# USB-to-ESP-UART_v3_1.net
KiCad netlist of a schematic drawn in EAGLE
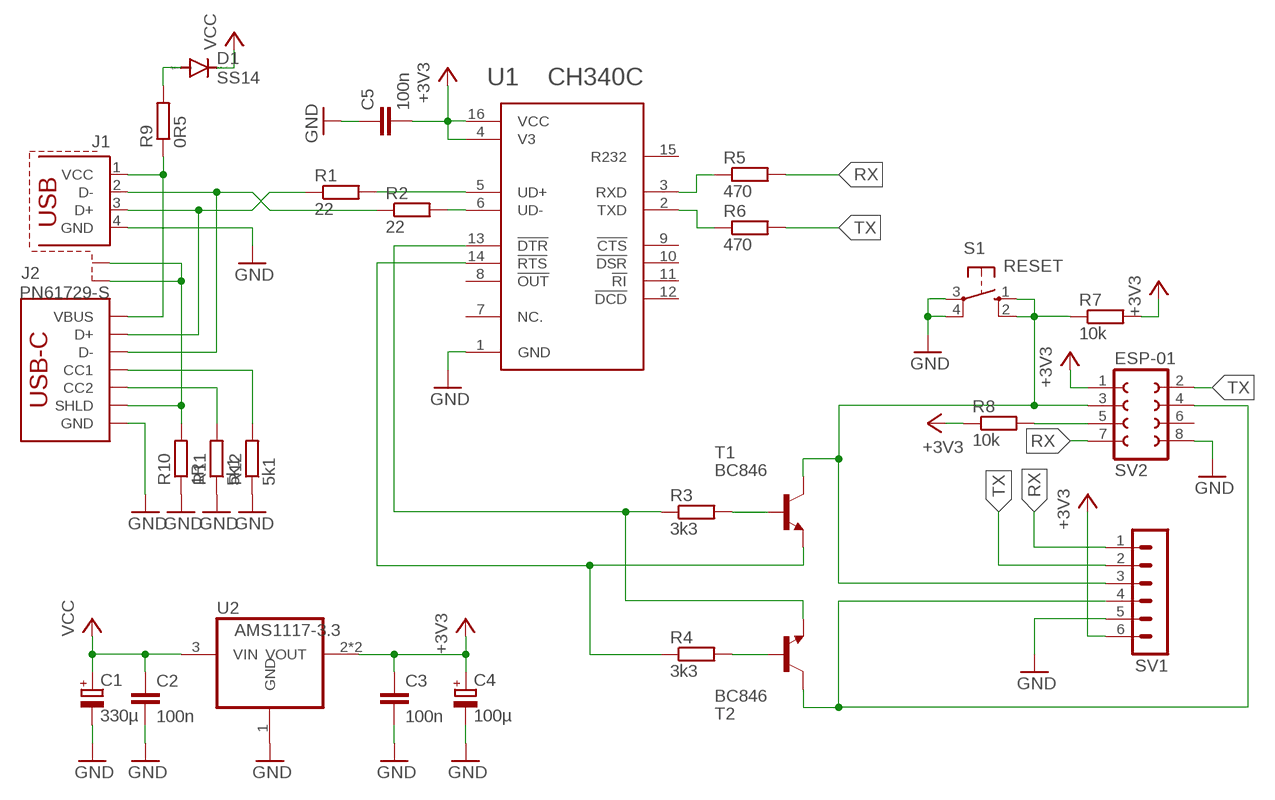
[diagram p0: schematic, sheet 1]

(export (version "E")
  (design (tool "Eeschema 10.0.6"))
  (components
    (comp (ref "C1")
      (value "330µ")
      (footprint "eagle-import:E2,5-7")
      (libsource (lib "eagle-import") (part "CPOL-EUE2.5-7"))
    )
    (comp (ref "C2")
      (value "100n")
      (footprint "eagle-import:C1206")
      (libsource (lib "eagle-import") (part "C-EUC1206"))
    )
    (comp (ref "C3")
      (value "100n")
      (footprint "eagle-import:C1206")
      (libsource (lib "eagle-import") (part "C-EUC1206"))
    )
    (comp (ref "C4")
      (value "100µ")
      (footprint "eagle-import:E2,5-5")
      (libsource (lib "eagle-import") (part "CPOL-EUE2.5-5"))
    )
    (comp (ref "C5")
      (value "100n")
      (footprint "eagle-import:C1206")
      (libsource (lib "eagle-import") (part "C-EUC1206"))
    )
    (comp (ref "D1")
      (value "SS14")
      (footprint "eagle-import:DO214AC")
      (libsource (lib "eagle-import") (part "DIODE-DO214AC"))
    )
    (comp (ref "J1")
      (value "PN61729-S")
      (footprint "eagle-import:PN61729-S")
      (libsource (lib "eagle-import") (part "PN61729-S"))
    )
    (comp (ref "J2")
      (value "USB_C_2-LAYER_PADS")
      (footprint "eagle-import:USB-C-16P-2LAYER-PADS")
      (libsource (lib "eagle-import") (part "USB_C_2-LAYER_PADS"))
    )
    (comp (ref "R1")
      (value "22")
      (footprint "eagle-import:R1206")
      (libsource (lib "eagle-import") (part "R-EU_R1206"))
    )
    (comp (ref "R2")
      (value "22")
      (footprint "eagle-import:R1206")
      (libsource (lib "eagle-import") (part "R-EU_R1206"))
    )
    (comp (ref "R3")
      (value "3k3")
      (footprint "eagle-import:R1206")
      (libsource (lib "eagle-import") (part "R-EU_R1206"))
    )
    (comp (ref "R4")
      (value "3k3")
      (footprint "eagle-import:R1206")
      (libsource (lib "eagle-import") (part "R-EU_R1206"))
    )
    (comp (ref "R5")
      (value "470")
      (footprint "eagle-import:R1206")
      (libsource (lib "eagle-import") (part "R-EU_R1206"))
    )
    (comp (ref "R6")
      (value "470")
      (footprint "eagle-import:R1206")
      (libsource (lib "eagle-import") (part "R-EU_R1206"))
    )
    (comp (ref "R7")
      (value "10k")
      (footprint "eagle-import:R1206")
      (libsource (lib "eagle-import") (part "R-EU_R1206"))
    )
    (comp (ref "R8")
      (value "10k")
      (footprint "eagle-import:R1206")
      (libsource (lib "eagle-import") (part "R-EU_R1206"))
    )
    (comp (ref "R9")
      (value "0R5")
      (footprint "eagle-import:R1206")
      (libsource (lib "eagle-import") (part "R-EU_R1206"))
    )
    (comp (ref "R10")
      (value "1R")
      (footprint "eagle-import:R1206")
      (libsource (lib "eagle-import") (part "R-EU_R1206"))
    )
    (comp (ref "R11")
      (value "5k1")
      (footprint "eagle-import:R1206")
      (libsource (lib "eagle-import") (part "R-EU_R1206"))
    )
    (comp (ref "R12")
      (value "5k1")
      (footprint "eagle-import:R1206")
      (libsource (lib "eagle-import") (part "R-EU_R1206"))
    )
    (comp (ref "S1")
      (value "RESET")
      (footprint "eagle-import:B3F-10XX")
      (fields (field (name "MPN") "B3F-1000"))
      (libsource (lib "eagle-import") (part "10-XX"))
    )
    (comp (ref "SV1")
      (value "MA06-1")
      (footprint "eagle-import:MA06-1")
      (libsource (lib "eagle-import") (part "MA06-1"))
    )
    (comp (ref "SV2")
      (value "ESP-01")
      (footprint "eagle-import:FE04-2-CL")
      (libsource (lib "eagle-import") (part "FE04-2CLEAN"))
    )
    (comp (ref "T1")
      (value "BC846")
      (footprint "eagle-import:SOT23-BEC")
      (libsource (lib "eagle-import") (part "-NPN-SOT23-BECBC846A"))
    )
    (comp (ref "T2")
      (value "BC846")
      (footprint "eagle-import:SOT23-BEC")
      (libsource (lib "eagle-import") (part "-NPN-SOT23-BECBC846A"))
    )
    (comp (ref "U1")
      (value "CH340C")
      (footprint "eagle-import:SOIC127P600X180-16N")
      (fields (field (name "MF") "WCH"))
      (libsource (lib "eagle-import") (part "CH340C"))
    )
    (comp (ref "U2")
      (value "AMS1117-3.3")
      (footprint "eagle-import:SOT223")
      (fields (field (name "MPN") "REG1117"))
      (libsource (lib "eagle-import") (part "REG1117"))
    )
  )
  (nets
    (net (code "1") (name "+3V3") (class "Default")
      (node (ref "C3") (pin "1") (pinfunction "1_1") (pintype "passive"))
      (node (ref "C4") (pin "+") (pinfunction "+_+") (pintype "passive"))
      (node (ref "C5") (pin "2") (pinfunction "2_2") (pintype "passive"))
      (node (ref "R7") (pin "2") (pinfunction "2_2") (pintype "passive"))
      (node (ref "R8") (pin "1") (pinfunction "1_1") (pintype "passive"))
      (node (ref "SV1") (pin "6") (pinfunction "6_6") (pintype "passive"))
      (node (ref "SV2") (pin "1") (pinfunction "1_1") (pintype "passive"))
      (node (ref "U1") (pin "16") (pinfunction "VCC_16") (pintype "power_in"))
      (node (ref "U1") (pin "4") (pinfunction "V3_4") (pintype "power_in"))
      (node (ref "U2") (pin "2") (pinfunction "VOUT_2") (pintype "output"))
      (node (ref "U2") (pin "4") (pinfunction "VOUT_4") (pintype "output"))
    )
    (net (code "2") (name "GND") (class "Default")
      (node (ref "C1") (pin "-") (pinfunction "-_-") (pintype "passive"))
      (node (ref "C2") (pin "2") (pinfunction "2_2") (pintype "passive"))
      (node (ref "C3") (pin "2") (pinfunction "2_2") (pintype "passive"))
      (node (ref "C4") (pin "-") (pinfunction "-_-") (pintype "passive"))
      (node (ref "C5") (pin "1") (pinfunction "1_1") (pintype "passive"))
      (node (ref "J1") (pin "4") (pinfunction "GND_4") (pintype "passive"))
      (node (ref "J2") (pin "GND") (pinfunction "GND_GND") (pintype "bidirectional"))
      (node (ref "J2") (pin "GND2") (pinfunction "GND_GND2") (pintype "bidirectional"))
      (node (ref "R10") (pin "1") (pinfunction "1_1") (pintype "passive"))
      (node (ref "R11") (pin "1") (pinfunction "1_1") (pintype "passive"))
      (node (ref "R12") (pin "1") (pinfunction "1_1") (pintype "passive"))
      (node (ref "S1") (pin "3") (pinfunction "P_3") (pintype "passive"))
      (node (ref "S1") (pin "4") (pinfunction "P1_4") (pintype "passive"))
      (node (ref "SV1") (pin "5") (pinfunction "5_5") (pintype "passive"))
      (node (ref "SV2") (pin "8") (pinfunction "8_8") (pintype "passive"))
      (node (ref "U1") (pin "1") (pinfunction "GND_1") (pintype "power_in"))
      (node (ref "U2") (pin "1") (pinfunction "GND_1") (pintype "power_in"))
    )
    (net (code "3") (name "Net-(D1-PadA)") (class "Default")
      (node (ref "D1") (pin "A") (pinfunction "A_A") (pintype "passive"))
      (node (ref "R9") (pin "2") (pinfunction "2_2") (pintype "passive"))
    )
    (net (code "4") (name "Net-(J1-D+)") (class "Default")
      (node (ref "J1") (pin "3") (pinfunction "D+_3") (pintype "passive"))
      (node (ref "J2") (pin "A6") (pinfunction "D+_A6") (pintype "bidirectional"))
      (node (ref "J2") (pin "B6") (pinfunction "D+_B6") (pintype "bidirectional"))
      (node (ref "R1") (pin "1") (pinfunction "1_1") (pintype "passive"))
    )
    (net (code "5") (name "Net-(J1-D-)") (class "Default")
      (node (ref "J1") (pin "2") (pinfunction "D-_2") (pintype "passive"))
      (node (ref "J2") (pin "A7") (pinfunction "D-_A7") (pintype "bidirectional"))
      (node (ref "J2") (pin "B7") (pinfunction "D-_B7") (pintype "bidirectional"))
      (node (ref "R2") (pin "1") (pinfunction "1_1") (pintype "passive"))
    )
    (net (code "6") (name "Net-(J1-PadS1)") (class "Default")
      (node (ref "J1") (pin "S1") (pinfunction "S1_S1") (pintype "passive"))
      (node (ref "J1") (pin "S2") (pinfunction "S2_S2") (pintype "passive"))
      (node (ref "J2") (pin "SHLD1") (pinfunction "SHLD_SHLD1") (pintype "bidirectional"))
      (node (ref "J2") (pin "SHLD2") (pinfunction "SHLD_SHLD2") (pintype "bidirectional"))
      (node (ref "J2") (pin "SHLD3") (pinfunction "SHLD_SHLD3") (pintype "bidirectional"))
      (node (ref "J2") (pin "SHLD4") (pinfunction "SHLD_SHLD4") (pintype "bidirectional"))
      (node (ref "R10") (pin "2") (pinfunction "2_2") (pintype "passive"))
    )
    (net (code "7") (name "Net-(J1-VCC)") (class "Default")
      (node (ref "J1") (pin "1") (pinfunction "VCC_1") (pintype "passive"))
      (node (ref "J2") (pin "VBUS1") (pinfunction "VBUS_VBUS1") (pintype "bidirectional"))
      (node (ref "J2") (pin "VBUS2") (pinfunction "VBUS_VBUS2") (pintype "bidirectional"))
      (node (ref "R9") (pin "1") (pinfunction "1_1") (pintype "passive"))
    )
    (net (code "8") (name "Net-(J2-CC1)") (class "Default")
      (node (ref "J2") (pin "A5") (pinfunction "CC1_A5") (pintype "bidirectional"))
      (node (ref "R12") (pin "2") (pinfunction "2_2") (pintype "passive"))
    )
    (net (code "9") (name "Net-(J2-CC2)") (class "Default")
      (node (ref "J2") (pin "B5") (pinfunction "CC2_B5") (pintype "bidirectional"))
      (node (ref "R11") (pin "2") (pinfunction "2_2") (pintype "passive"))
    )
    (net (code "10") (name "Net-(R3-Pad2)") (class "Default")
      (node (ref "R3") (pin "2") (pinfunction "2_2") (pintype "passive"))
      (node (ref "T1") (pin "B") (pinfunction "B_B") (pintype "passive"))
    )
    (net (code "11") (name "Net-(R4-Pad2)") (class "Default")
      (node (ref "R4") (pin "2") (pinfunction "2_2") (pintype "passive"))
      (node (ref "T2") (pin "B") (pinfunction "B_B") (pintype "passive"))
    )
    (net (code "12") (name "Net-(R8-Pad2)") (class "Default")
      (node (ref "R8") (pin "2") (pinfunction "2_2") (pintype "passive"))
      (node (ref "SV2") (pin "5") (pinfunction "5_5") (pintype "passive"))
    )
    (net (code "13") (name "Net-(S1-S)") (class "Default")
      (node (ref "R7") (pin "1") (pinfunction "1_1") (pintype "passive"))
      (node (ref "S1") (pin "1") (pinfunction "S_1") (pintype "passive"))
      (node (ref "S1") (pin "2") (pinfunction "S1_2") (pintype "passive"))
      (node (ref "SV1") (pin "3") (pinfunction "3_3") (pintype "passive"))
      (node (ref "SV2") (pin "3") (pinfunction "3_3") (pintype "passive"))
      (node (ref "T1") (pin "C") (pinfunction "C_C") (pintype "passive"))
    )
    (net (code "14") (name "Net-(SV1-Pad4)") (class "Default")
      (node (ref "SV1") (pin "4") (pinfunction "4_4") (pintype "passive"))
      (node (ref "SV2") (pin "4") (pinfunction "4_4") (pintype "passive"))
      (node (ref "T2") (pin "C") (pinfunction "C_C") (pintype "passive"))
    )
    (net (code "15") (name "Net-(U1-RXD)") (class "Default")
      (node (ref "R5") (pin "1") (pinfunction "1_1") (pintype "passive"))
      (node (ref "U1") (pin "3") (pinfunction "RXD_3") (pintype "input"))
    )
    (net (code "16") (name "Net-(U1-TXD)") (class "Default")
      (node (ref "R6") (pin "1") (pinfunction "1_1") (pintype "passive"))
      (node (ref "U1") (pin "2") (pinfunction "TXD_2") (pintype "output"))
    )
    (net (code "17") (name "Net-(U1-UD+)") (class "Default")
      (node (ref "R1") (pin "2") (pinfunction "2_2") (pintype "passive"))
      (node (ref "U1") (pin "5") (pinfunction "UD+_5") (pintype "bidirectional"))
    )
    (net (code "18") (name "Net-(U1-UD-)") (class "Default")
      (node (ref "R2") (pin "2") (pinfunction "2_2") (pintype "passive"))
      (node (ref "U1") (pin "6") (pinfunction "UD-_6") (pintype "bidirectional"))
    )
    (net (code "19") (name "Net-(U1-~{DTR})") (class "Default")
      (node (ref "R3") (pin "1") (pinfunction "1_1") (pintype "passive"))
      (node (ref "T2") (pin "E") (pinfunction "E_E") (pintype "passive"))
      (node (ref "U1") (pin "13") (pinfunction "~{DTR}_13") (pintype "output"))
    )
    (net (code "20") (name "Net-(U1-~{RTS})") (class "Default")
      (node (ref "R4") (pin "1") (pinfunction "1_1") (pintype "passive"))
      (node (ref "T1") (pin "E") (pinfunction "E_E") (pintype "passive"))
      (node (ref "U1") (pin "14") (pinfunction "~{RTS}_14") (pintype "output"))
    )
    (net (code "21") (name "RX") (class "Default")
      (node (ref "R5") (pin "2") (pinfunction "2_2") (pintype "passive"))
      (node (ref "SV1") (pin "1") (pinfunction "1_1") (pintype "passive"))
      (node (ref "SV2") (pin "7") (pinfunction "7_7") (pintype "passive"))
    )
    (net (code "22") (name "TX") (class "Default")
      (node (ref "R6") (pin "2") (pinfunction "2_2") (pintype "passive"))
      (node (ref "SV1") (pin "2") (pinfunction "2_2") (pintype "passive"))
      (node (ref "SV2") (pin "2") (pinfunction "2_2") (pintype "passive"))
    )
    (net (code "23") (name "VCC") (class "Default")
      (node (ref "C1") (pin "+") (pinfunction "+_+") (pintype "passive"))
      (node (ref "C2") (pin "1") (pinfunction "1_1") (pintype "passive"))
      (node (ref "D1") (pin "C") (pinfunction "C_C") (pintype "passive"))
      (node (ref "U2") (pin "3") (pinfunction "VIN_3") (pintype "input"))
    )
    (net (code "24") (name "unconnected-(SV2-Pad6)") (class "Default")
      (node (ref "SV2") (pin "6") (pinfunction "6_6") (pintype "passive"))
    )
    (net (code "25") (name "unconnected-(U1-NC.-Pad7)") (class "Default")
      (node (ref "U1") (pin "7") (pinfunction "NC._7") (pintype "no_connect"))
    )
    (net (code "26") (name "unconnected-(U1-R232-Pad15)") (class "Default")
      (node (ref "U1") (pin "15") (pinfunction "R232_15") (pintype "input"))
    )
    (net (code "27") (name "unconnected-(U1-~{CTS}-Pad9)") (class "Default")
      (node (ref "U1") (pin "9") (pinfunction "~{CTS}_9") (pintype "input"))
    )
    (net (code "28") (name "unconnected-(U1-~{DCD}-Pad12)") (class "Default")
      (node (ref "U1") (pin "12") (pinfunction "~{DCD}_12") (pintype "input"))
    )
    (net (code "29") (name "unconnected-(U1-~{DSR}-Pad10)") (class "Default")
      (node (ref "U1") (pin "10") (pinfunction "~{DSR}_10") (pintype "input"))
    )
    (net (code "30") (name "unconnected-(U1-~{OUT}-Pad8)") (class "Default")
      (node (ref "U1") (pin "8") (pinfunction "~{OUT}_8") (pintype "output"))
    )
    (net (code "31") (name "unconnected-(U1-~{RI}-Pad11)") (class "Default")
      (node (ref "U1") (pin "11") (pinfunction "~{RI}_11") (pintype "input"))
    )
  )
)
